# Sensor.net
KiCad netlist of a schematic drawn in Altium Designer
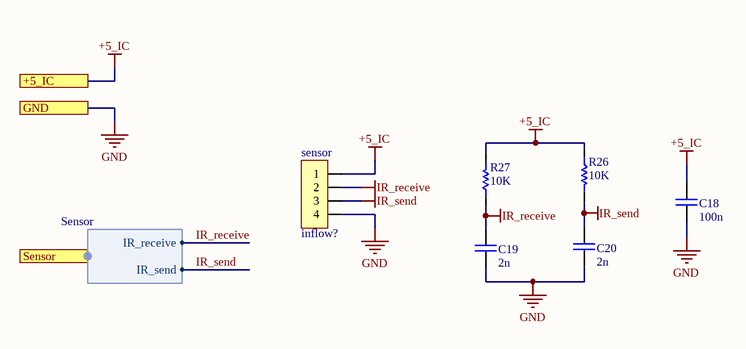
[diagram p0: Sensor.SchDoc]

(export (version "E")
  (design (tool "Eeschema 10.0.6"))
  (components
    (comp (ref "C18")
      (value "100n")
      (footprint "CAP 1206/3216")
      (description "Bipolar ceramic capacitor SMD")
      (fields (field (name "VALIDATION") "Valid"))
      (libsource (lib "aKaReZa") (part "Cap_Multi_SMD_100nF_1206"))
    )
    (comp (ref "C19")
      (value "2n")
      (footprint "CAP 1206/3216")
      (description "Bipolar ceramic capacitor SMD")
      (fields (field (name "VALIDATION") "Valid"))
      (libsource (lib "aKaReZa") (part "Cap_Multi_SMD_100nF_1206"))
    )
    (comp (ref "C20")
      (value "2n")
      (footprint "CAP 1206/3216")
      (description "Bipolar ceramic capacitor SMD")
      (fields (field (name "VALIDATION") "Valid"))
      (libsource (lib "aKaReZa") (part "Cap_Multi_SMD_100nF_1206"))
    )
    (comp (ref "R26")
      (value "10K")
      (footprint "RES 1206 (3216X08L)")
      (description "Resistor")
      (fields (field (name "VALIDATION") "Valid"))
      (libsource (lib "aKaReZa") (part "Res_SMD_1206"))
    )
    (comp (ref "R27")
      (value "10K")
      (footprint "RES 1206 (3216X08L)")
      (description "Resistor")
      (fields (field (name "VALIDATION") "Valid"))
      (libsource (lib "aKaReZa") (part "Res_SMD_1206"))
    )
    (comp (ref "sensor")
      (value "4'Pin")
      (footprint "MOLEX KK 0022272041")
      (description "Signal Connector 4'Pin")
      (fields (field (name "INFLOW") "inflow?") (field (name "VALIDATION") "Valid"))
      (libsource (lib "aKaReZa") (part "Con_Signal_4"))
    )
  )
  (nets
    (net (code "2") (name "+5_IC") (class "Default")
      (node (ref "C18") (pin "1") (pinfunction "1_1") (pintype "passive"))
      (node (ref "R26") (pin "1") (pinfunction "1_1") (pintype "passive"))
      (node (ref "R27") (pin "2") (pinfunction "2_2") (pintype "passive"))
      (node (ref "sensor") (pin "1") (pinfunction "1_1") (pintype "passive"))
    )
    (net (code "4") (name "GND") (class "Default")
      (node (ref "C18") (pin "2") (pinfunction "2_2") (pintype "passive"))
      (node (ref "C19") (pin "2") (pinfunction "2_2") (pintype "passive"))
      (node (ref "C20") (pin "2") (pinfunction "2_2") (pintype "passive"))
      (node (ref "sensor") (pin "4") (pinfunction "4_4") (pintype "passive"))
    )
    (net (code "5") (name "IR_receive") (class "Default")
      (node (ref "C19") (pin "1") (pinfunction "1_1") (pintype "passive"))
      (node (ref "R27") (pin "1") (pinfunction "1_1") (pintype "passive"))
      (node (ref "sensor") (pin "2") (pinfunction "2_2") (pintype "passive"))
    )
    (net (code "6") (name "IR_send") (class "Default")
      (node (ref "C20") (pin "1") (pinfunction "1_1") (pintype "passive"))
      (node (ref "R26") (pin "2") (pinfunction "2_2") (pintype "passive"))
      (node (ref "sensor") (pin "3") (pinfunction "3_3") (pintype "passive"))
    )
  )
)
